# Adafruit_Feather_M0_AdaloggerTPS63001.net
KiCad netlist of a schematic drawn in EAGLE
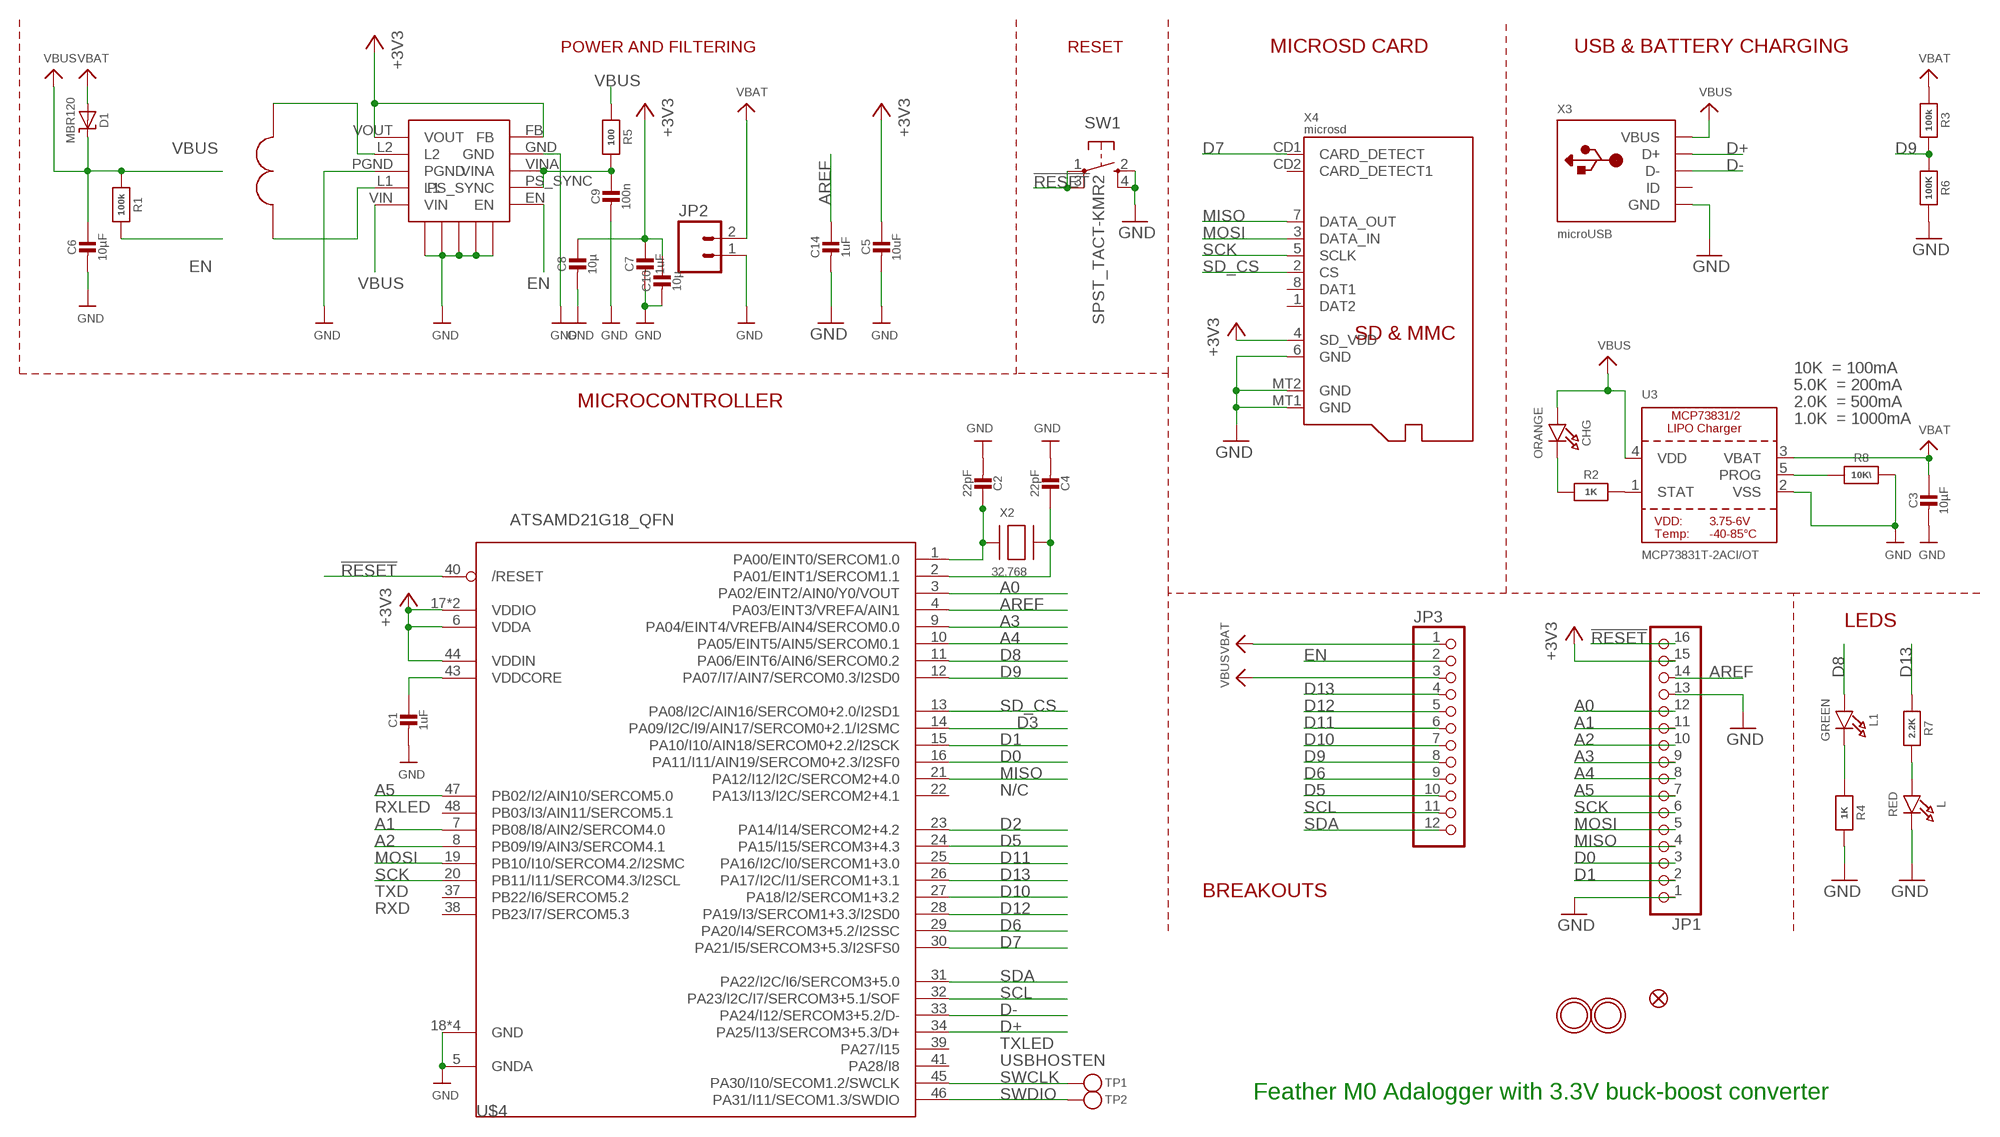
[diagram p0: schematic, sheet 1]

(export (version "E")
  (design (tool "Eeschema 10.0.6"))
  (components
    (comp (ref "C1")
      (value "1uF")
      (footprint "eagle-import:0603-NO")
      (libsource (lib "eagle-import") (part "CAP_CERAMIC0603_NO"))
    )
    (comp (ref "C2")
      (value "22pF")
      (footprint "eagle-import:0603-NO")
      (libsource (lib "eagle-import") (part "CAP_CERAMIC0603_NO"))
    )
    (comp (ref "C3")
      (value "10µF")
      (footprint "eagle-import:0805-NO")
      (libsource (lib "eagle-import") (part "CAP_CERAMIC0805-NOOUTLINE"))
    )
    (comp (ref "C4")
      (value "22pF")
      (footprint "eagle-import:0603-NO")
      (libsource (lib "eagle-import") (part "CAP_CERAMIC0603_NO"))
    )
    (comp (ref "C5")
      (value "10uF")
      (footprint "eagle-import:0805-NO")
      (libsource (lib "eagle-import") (part "CAP_CERAMIC0805-NOOUTLINE"))
    )
    (comp (ref "C6")
      (value "10µF")
      (footprint "eagle-import:0805-NO")
      (libsource (lib "eagle-import") (part "CAP_CERAMIC0805-NOOUTLINE"))
    )
    (comp (ref "C7")
      (value "1uF")
      (footprint "eagle-import:0603-NO")
      (libsource (lib "eagle-import") (part "CAP_CERAMIC0603_NO"))
    )
    (comp (ref "C8")
      (value "10µ")
      (footprint "eagle-import:0603-NO")
      (libsource (lib "eagle-import") (part "CAP_CERAMIC0603_NO"))
    )
    (comp (ref "C9")
      (value "100n")
      (footprint "eagle-import:0603-NO")
      (libsource (lib "eagle-import") (part "CAP_CERAMIC0603_NO"))
    )
    (comp (ref "C10")
      (value "10µ")
      (footprint "eagle-import:0603-NO")
      (libsource (lib "eagle-import") (part "CAP_CERAMIC0603_NO"))
    )
    (comp (ref "C14")
      (value "1uF")
      (footprint "eagle-import:0603-NO")
      (libsource (lib "eagle-import") (part "CAP_CERAMIC0603_NO"))
    )
    (comp (ref "CHG")
      (value "ORANGE")
      (footprint "eagle-import:CHIPLED_0805_NOOUTLINE")
      (libsource (lib "eagle-import") (part "LED0805_NOOUTLINE"))
    )
    (comp (ref "D1")
      (value "MBR120")
      (footprint "eagle-import:SOD-123")
      (libsource (lib "eagle-import") (part "DIODE-SCHOTTKYSOD-123"))
    )
    (comp (ref "JP1")
      (value "HEADER-1X16ROUND")
      (footprint "eagle-import:1X16_ROUND")
      (libsource (lib "eagle-import") (part "HEADER-1X16ROUND"))
    )
    (comp (ref "JP2")
      (value "M02PTH")
      (footprint "eagle-import:1X02")
      (libsource (lib "eagle-import") (part "M02PTH"))
    )
    (comp (ref "JP3")
      (value "HEADER-1X12")
      (footprint "eagle-import:1X12_ROUND")
      (libsource (lib "eagle-import") (part "HEADER-1X12"))
    )
    (comp (ref "L")
      (value "RED")
      (footprint "eagle-import:CHIPLED_0805_NOOUTLINE")
      (libsource (lib "eagle-import") (part "LED0805_NOOUTLINE"))
    )
    (comp (ref "L1")
      (value "GREEN")
      (footprint "eagle-import:CHIPLED_0805_NOOUTLINE")
      (libsource (lib "eagle-import") (part "LED0805_NOOUTLINE"))
    )
    (comp (ref "R1")
      (value "100k")
      (footprint "eagle-import:0603-NO")
      (libsource (lib "eagle-import") (part "RESISTOR_0603_NOOUT"))
    )
    (comp (ref "R2")
      (value "1K")
      (footprint "eagle-import:0603-NO")
      (libsource (lib "eagle-import") (part "RESISTOR_0603_NOOUT"))
    )
    (comp (ref "R3")
      (value "100k")
      (footprint "eagle-import:0603-NO")
      (libsource (lib "eagle-import") (part "RESISTOR_0603_NOOUT"))
    )
    (comp (ref "R4")
      (value "1K")
      (footprint "eagle-import:0603-NO")
      (libsource (lib "eagle-import") (part "RESISTOR_0603_NOOUT"))
    )
    (comp (ref "R5")
      (value "100")
      (footprint "eagle-import:0603-NO")
      (libsource (lib "eagle-import") (part "RESISTOR_0603_NOOUT"))
    )
    (comp (ref "R6")
      (value "100K")
      (footprint "eagle-import:0603-NO")
      (libsource (lib "eagle-import") (part "RESISTOR_0603_NOOUT"))
    )
    (comp (ref "R7")
      (value "2.2K")
      (footprint "eagle-import:0603-NO")
      (libsource (lib "eagle-import") (part "RESISTOR_0603_NOOUT"))
    )
    (comp (ref "R8")
      (value "10K\\")
      (footprint "eagle-import:0603-NO")
      (libsource (lib "eagle-import") (part "RESISTOR_0603_NOOUT"))
    )
    (comp (ref "SW1")
      (value "SPST_TACT-KMR2")
      (footprint "eagle-import:KMR2")
      (libsource (lib "eagle-import") (part "SPST_TACT-KMR2"))
    )
    (comp (ref "TP1")
      (value "TESTPOINTROUND1.5MM")
      (footprint "eagle-import:TESTPOINT_ROUND_1.5MM")
      (libsource (lib "eagle-import") (part "TESTPOINTROUND1.5MM"))
    )
    (comp (ref "TP2")
      (value "TESTPOINTROUND1.5MM")
      (footprint "eagle-import:TESTPOINT_ROUND_1.5MM")
      (libsource (lib "eagle-import") (part "TESTPOINTROUND1.5MM"))
    )
    (comp (ref "U$4")
      (value "ATSAMD21G18_QFN")
      (footprint "eagle-import:TQFN48_7MM")
      (libsource (lib "eagle-import") (part "ATSAMD21J_QFN"))
    )
    (comp (ref "U$12")
      (value "TPS63001")
      (footprint "eagle-import:TPS63001")
      (libsource (lib "eagle-import") (part "TPS63001"))
    )
    (comp (ref "U$15")
      (value "VLF4012A")
      (footprint "eagle-import:VLF4012A")
      (libsource (lib "eagle-import") (part "VLF4012A"))
    )
    (comp (ref "U$31")
      (value "MOUNTINGHOLE2.5")
      (footprint "eagle-import:MOUNTINGHOLE_2.5_PLATED")
      (libsource (lib "eagle-import") (part "MOUNTINGHOLE2.5"))
    )
    (comp (ref "U$32")
      (value "MOUNTINGHOLE2.5")
      (footprint "eagle-import:MOUNTINGHOLE_2.5_PLATED")
      (libsource (lib "eagle-import") (part "MOUNTINGHOLE2.5"))
    )
    (comp (ref "U$35")
      (value "FIDUCIAL\"\"")
      (footprint "eagle-import:FIDUCIAL_1MM")
      (libsource (lib "eagle-import") (part "FIDUCIAL{dblquote}{dblquote}"))
    )
    (comp (ref "U3")
      (value "MCP73831T-2ACI/OT")
      (footprint "eagle-import:SOT23-5")
      (libsource (lib "eagle-import") (part "MCP73831/2"))
    )
    (comp (ref "X2")
      (value "32.768")
      (footprint "eagle-import:XTAL3215")
      (libsource (lib "eagle-import") (part "XTAL-3.2X1.5"))
    )
    (comp (ref "X3")
      (value "microUSB")
      (footprint "eagle-import:4UCONN_20329_V2")
      (libsource (lib "eagle-import") (part "USB_MICRO_20329_V2"))
    )
    (comp (ref "X4")
      (value "microsd")
      (footprint "eagle-import:MICROSD")
      (libsource (lib "eagle-import") (part "MICROSD"))
    )
  )
  (nets
    (net (code "1") (name "+3V3") (class "Default")
      (node (ref "C10") (pin "1") (pinfunction "1_1") (pintype "passive"))
      (node (ref "C5") (pin "1") (pinfunction "1_1") (pintype "passive"))
      (node (ref "C7") (pin "1") (pinfunction "1_1") (pintype "passive"))
      (node (ref "C8") (pin "1") (pinfunction "1_1") (pintype "passive"))
      (node (ref "JP1") (pin "15") (pinfunction "15_15") (pintype "passive"))
      (node (ref "U$12") (pin "FB") (pinfunction "FB_FB") (pintype "bidirectional"))
      (node (ref "U$12") (pin "VOUT") (pinfunction "VOUT_VOUT") (pintype "bidirectional"))
      (node (ref "U$4") (pin "17") (pinfunction "VDDIO_17") (pintype "power_in"))
      (node (ref "U$4") (pin "36") (pinfunction "VDDIO_36") (pintype "power_in"))
      (node (ref "U$4") (pin "44") (pinfunction "VDDIN_44") (pintype "power_in"))
      (node (ref "U$4") (pin "6") (pinfunction "VDDA_6") (pintype "power_in"))
      (node (ref "X4") (pin "4") (pinfunction "SD_VDD_4") (pintype "power_in"))
    )
    (net (code "2") (name "/A0") (class "Default")
      (node (ref "JP1") (pin "12") (pinfunction "12_12") (pintype "passive"))
      (node (ref "U$4") (pin "3") (pinfunction "PA02/EINT2/AIN0/Y0/VOUT_3") (pintype "bidirectional"))
    )
    (net (code "3") (name "/A1") (class "Default")
      (node (ref "JP1") (pin "11") (pinfunction "11_11") (pintype "passive"))
      (node (ref "U$4") (pin "7") (pinfunction "PB08/I8/AIN2/SERCOM4.0_7") (pintype "bidirectional"))
    )
    (net (code "4") (name "/A2") (class "Default")
      (node (ref "JP1") (pin "10") (pinfunction "10_10") (pintype "passive"))
      (node (ref "U$4") (pin "8") (pinfunction "PB09/I9/AIN3/SERCOM4.1_8") (pintype "bidirectional"))
    )
    (net (code "5") (name "/A3") (class "Default")
      (node (ref "JP1") (pin "9") (pinfunction "9_9") (pintype "passive"))
      (node (ref "U$4") (pin "9") (pinfunction "PA04/EINT4/VREFB/AIN4/SERCOM0.0_9") (pintype "bidirectional"))
    )
    (net (code "6") (name "/A4") (class "Default")
      (node (ref "JP1") (pin "8") (pinfunction "8_8") (pintype "passive"))
      (node (ref "U$4") (pin "10") (pinfunction "PA05/EINT5/AIN5/SERCOM0.1_10") (pintype "bidirectional"))
    )
    (net (code "7") (name "/A5") (class "Default")
      (node (ref "JP1") (pin "7") (pinfunction "7_7") (pintype "passive"))
      (node (ref "U$4") (pin "47") (pinfunction "PB02/I2/AIN10/SERCOM5.0_47") (pintype "bidirectional"))
    )
    (net (code "8") (name "/AREF") (class "Default")
      (node (ref "C14") (pin "1") (pinfunction "1_1") (pintype "passive"))
      (node (ref "JP1") (pin "14") (pinfunction "14_14") (pintype "passive"))
      (node (ref "U$4") (pin "4") (pinfunction "PA03/EINT3/VREFA/AIN1_4") (pintype "bidirectional"))
    )
    (net (code "9") (name "/D+") (class "Default")
      (node (ref "U$4") (pin "34") (pinfunction "PA25/I13/SERCOM3+5.3/D+_34") (pintype "bidirectional"))
      (node (ref "X3") (pin "D+") (pinfunction "D+_D+") (pintype "bidirectional"))
    )
    (net (code "10") (name "/D-") (class "Default")
      (node (ref "U$4") (pin "33") (pinfunction "PA24/I12/SERCOM3+5.2/D-_33") (pintype "bidirectional"))
      (node (ref "X3") (pin "D-") (pinfunction "D-_D-") (pintype "bidirectional"))
    )
    (net (code "11") (name "/D0") (class "Default")
      (node (ref "JP1") (pin "3") (pinfunction "3_3") (pintype "passive"))
      (node (ref "U$4") (pin "16") (pinfunction "PA11/I11/AIN19/SERCOM0+2.3/I2SF0_16") (pintype "bidirectional"))
    )
    (net (code "12") (name "/D1") (class "Default")
      (node (ref "JP1") (pin "2") (pinfunction "2_2") (pintype "passive"))
      (node (ref "U$4") (pin "15") (pinfunction "PA10/I10/AIN18/SERCOM0+2.2/I2SCK_15") (pintype "bidirectional"))
    )
    (net (code "13") (name "/D2") (class "Default")
      (node (ref "U$4") (pin "23") (pinfunction "PA14/I14/SERCOM2+4.2_23") (pintype "bidirectional"))
    )
    (net (code "14") (name "/D3") (class "Default")
      (node (ref "U$4") (pin "14") (pinfunction "PA09/I2C/I9/AIN17/SERCOM0+2.1/I2SMC_14") (pintype "bidirectional"))
    )
    (net (code "15") (name "/D5") (class "Default")
      (node (ref "JP3") (pin "10") (pinfunction "10_10") (pintype "passive"))
      (node (ref "U$4") (pin "24") (pinfunction "PA15/I15/SERCOM3+4.3_24") (pintype "bidirectional"))
    )
    (net (code "16") (name "/D6") (class "Default")
      (node (ref "JP3") (pin "9") (pinfunction "9_9") (pintype "passive"))
      (node (ref "U$4") (pin "29") (pinfunction "PA20/I4/SERCOM3+5.2/I2SSC_29") (pintype "bidirectional"))
    )
    (net (code "17") (name "/D7") (class "Default")
      (node (ref "U$4") (pin "30") (pinfunction "PA21/I5/SERCOM3+5.3/I2SFS0_30") (pintype "bidirectional"))
      (node (ref "X4") (pin "CD1") (pinfunction "CARD_DETECT_CD1") (pintype "passive"))
    )
    (net (code "18") (name "/D8") (class "Default")
      (node (ref "L1") (pin "A") (pinfunction "A_A") (pintype "passive"))
      (node (ref "U$4") (pin "11") (pinfunction "PA06/EINT6/AIN6/SERCOM0.2_11") (pintype "bidirectional"))
    )
    (net (code "19") (name "/D9") (class "Default")
      (node (ref "JP3") (pin "8") (pinfunction "8_8") (pintype "passive"))
      (node (ref "R3") (pin "2") (pinfunction "2_2") (pintype "passive"))
      (node (ref "R6") (pin "1") (pinfunction "1_1") (pintype "passive"))
      (node (ref "U$4") (pin "12") (pinfunction "PA07/I7/AIN7/SERCOM0.3/I2SD0_12") (pintype "bidirectional"))
    )
    (net (code "20") (name "/D10") (class "Default")
      (node (ref "JP3") (pin "7") (pinfunction "7_7") (pintype "passive"))
      (node (ref "U$4") (pin "27") (pinfunction "PA18/I2/SERCOM1+3.2_27") (pintype "bidirectional"))
    )
    (net (code "21") (name "/D11") (class "Default")
      (node (ref "JP3") (pin "6") (pinfunction "6_6") (pintype "passive"))
      (node (ref "U$4") (pin "25") (pinfunction "PA16/I2C/I0/SERCOM1+3.0_25") (pintype "bidirectional"))
    )
    (net (code "22") (name "/D12") (class "Default")
      (node (ref "JP3") (pin "5") (pinfunction "5_5") (pintype "passive"))
      (node (ref "U$4") (pin "28") (pinfunction "PA19/I3/SERCOM1+3.3/I2SD0_28") (pintype "bidirectional"))
    )
    (net (code "23") (name "/D13") (class "Default")
      (node (ref "JP3") (pin "4") (pinfunction "4_4") (pintype "passive"))
      (node (ref "R7") (pin "1") (pinfunction "1_1") (pintype "passive"))
      (node (ref "U$4") (pin "26") (pinfunction "PA17/I2C/I1/SERCOM1+3.1_26") (pintype "bidirectional"))
    )
    (net (code "24") (name "/EN") (class "Default")
      (node (ref "JP3") (pin "2") (pinfunction "2_2") (pintype "passive"))
      (node (ref "R1") (pin "2") (pinfunction "2_2") (pintype "passive"))
      (node (ref "U$12") (pin "EN") (pinfunction "EN_EN") (pintype "bidirectional"))
    )
    (net (code "25") (name "/MISO") (class "Default")
      (node (ref "JP1") (pin "4") (pinfunction "4_4") (pintype "passive"))
      (node (ref "U$4") (pin "21") (pinfunction "PA12/I12/I2C/SERCOM2+4.0_21") (pintype "bidirectional"))
      (node (ref "X4") (pin "7") (pinfunction "DATA_OUT_7") (pintype "output"))
    )
    (net (code "26") (name "/MOSI") (class "Default")
      (node (ref "JP1") (pin "5") (pinfunction "5_5") (pintype "passive"))
      (node (ref "U$4") (pin "19") (pinfunction "PB10/I10/SERCOM4.2/I2SMC_19") (pintype "bidirectional"))
      (node (ref "X4") (pin "3") (pinfunction "DATA_IN_3") (pintype "input"))
    )
    (net (code "27") (name "/SCK") (class "Default")
      (node (ref "JP1") (pin "6") (pinfunction "6_6") (pintype "passive"))
      (node (ref "U$4") (pin "20") (pinfunction "PB11/I11/SERCOM4.3/I2SCL_20") (pintype "bidirectional"))
      (node (ref "X4") (pin "5") (pinfunction "SCLK_5") (pintype "input"))
    )
    (net (code "28") (name "/SCL") (class "Default")
      (node (ref "JP3") (pin "11") (pinfunction "11_11") (pintype "passive"))
      (node (ref "U$4") (pin "32") (pinfunction "PA23/I2C/I7/SERCOM3+5.1/SOF_32") (pintype "bidirectional"))
    )
    (net (code "29") (name "/SDA") (class "Default")
      (node (ref "JP3") (pin "12") (pinfunction "12_12") (pintype "passive"))
      (node (ref "U$4") (pin "31") (pinfunction "PA22/I2C/I6/SERCOM3+5.0_31") (pintype "bidirectional"))
    )
    (net (code "30") (name "/SD_CS") (class "Default")
      (node (ref "U$4") (pin "13") (pinfunction "PA08/I2C/AIN16/SERCOM0+2.0/I2SD1_13") (pintype "bidirectional"))
      (node (ref "X4") (pin "2") (pinfunction "CS_2") (pintype "input"))
    )
    (net (code "31") (name "/SWCLK") (class "Default")
      (node (ref "TP1") (pin "P$1") (pinfunction "P$1_P$1") (pintype "bidirectional"))
      (node (ref "U$4") (pin "45") (pinfunction "PA30/I10/SECOM1.2/SWCLK_45") (pintype "bidirectional"))
    )
    (net (code "32") (name "/SWDIO") (class "Default")
      (node (ref "TP2") (pin "P$1") (pinfunction "P$1_P$1") (pintype "bidirectional"))
      (node (ref "U$4") (pin "46") (pinfunction "PA31/I11/SECOM1.3/SWDIO_46") (pintype "bidirectional"))
    )
    (net (code "33") (name "/~{RESET}") (class "Default")
      (node (ref "JP1") (pin "16") (pinfunction "16_16") (pintype "passive"))
      (node (ref "SW1") (pin "1") (pinfunction "P_1") (pintype "passive"))
      (node (ref "SW1") (pin "3") (pinfunction "P1_3") (pintype "passive"))
      (node (ref "U$4") (pin "40") (pinfunction "/RESET_40") (pintype "bidirectional"))
    )
    (net (code "34") (name "GND") (class "Default")
      (node (ref "C1") (pin "2") (pinfunction "2_2") (pintype "passive"))
      (node (ref "C10") (pin "2") (pinfunction "2_2") (pintype "passive"))
      (node (ref "C14") (pin "2") (pinfunction "2_2") (pintype "passive"))
      (node (ref "C2") (pin "2") (pinfunction "2_2") (pintype "passive"))
      (node (ref "C3") (pin "2") (pinfunction "2_2") (pintype "passive"))
      (node (ref "C4") (pin "2") (pinfunction "2_2") (pintype "passive"))
      (node (ref "C5") (pin "2") (pinfunction "2_2") (pintype "passive"))
      (node (ref "C6") (pin "2") (pinfunction "2_2") (pintype "passive"))
      (node (ref "C7") (pin "2") (pinfunction "2_2") (pintype "passive"))
      (node (ref "C8") (pin "2") (pinfunction "2_2") (pintype "passive"))
      (node (ref "C9") (pin "2") (pinfunction "2_2") (pintype "passive"))
      (node (ref "JP1") (pin "1") (pinfunction "1_1") (pintype "passive"))
      (node (ref "JP1") (pin "13") (pinfunction "13_13") (pintype "passive"))
      (node (ref "JP2") (pin "1") (pinfunction "1_1") (pintype "passive"))
      (node (ref "L") (pin "C") (pinfunction "C_C") (pintype "passive"))
      (node (ref "R4") (pin "2") (pinfunction "2_2") (pintype "passive"))
      (node (ref "R6") (pin "2") (pinfunction "2_2") (pintype "passive"))
      (node (ref "R8") (pin "2") (pinfunction "2_2") (pintype "passive"))
      (node (ref "SW1") (pin "2") (pinfunction "S_2") (pintype "passive"))
      (node (ref "SW1") (pin "4") (pinfunction "S1_4") (pintype "passive"))
      (node (ref "U$12") (pin "GND") (pinfunction "GND_GND") (pintype "bidirectional"))
      (node (ref "U$12") (pin "GNDP1") (pinfunction "GNDP1_GNDP1") (pintype "bidirectional"))
      (node (ref "U$12") (pin "GNDP2") (pinfunction "GNDP2_GNDP2") (pintype "bidirectional"))
      (node (ref "U$12") (pin "GNDP3") (pinfunction "GNDP3_GNDP3") (pintype "bidirectional"))
      (node (ref "U$12") (pin "GNDP4") (pinfunction "GNDP4_GNDP4") (pintype "bidirectional"))
      (node (ref "U$12") (pin "GNDP5") (pinfunction "GNDP5_GNDP5") (pintype "bidirectional"))
      (node (ref "U$12") (pin "PGND") (pinfunction "PGND_PGND") (pintype "bidirectional"))
      (node (ref "U$4") (pin "18") (pinfunction "GND_18") (pintype "power_in"))
      (node (ref "U$4") (pin "35") (pinfunction "GND_35") (pintype "power_in"))
      (node (ref "U$4") (pin "42") (pinfunction "GND_42") (pintype "power_in"))
      (node (ref "U$4") (pin "5") (pinfunction "GNDA_5") (pintype "power_in"))
      (node (ref "U$4") (pin "THERMAL") (pinfunction "GND_THERMAL") (pintype "power_in"))
      (node (ref "U3") (pin "2") (pinfunction "VSS_2") (pintype "power_in"))
      (node (ref "X3") (pin "BASE@1") (pinfunction "GND_BASE@1") (pintype "power_in"))
      (node (ref "X3") (pin "BASE@2") (pinfunction "GND_BASE@2") (pintype "power_in"))
      (node (ref "X3") (pin "GND") (pinfunction "GND_GND") (pintype "power_in"))
      (node (ref "X3") (pin "SPRT@1") (pinfunction "GND_SPRT@1") (pintype "power_in"))
      (node (ref "X3") (pin "SPRT@2") (pinfunction "GND_SPRT@2") (pintype "power_in"))
      (node (ref "X3") (pin "SPRT@3") (pinfunction "GND_SPRT@3") (pintype "power_in"))
      (node (ref "X3") (pin "SPRT@4") (pinfunction "GND_SPRT@4") (pintype "power_in"))
      (node (ref "X4") (pin "6") (pinfunction "GND_6") (pintype "power_in"))
      (node (ref "X4") (pin "MT1") (pinfunction "GND_MT1") (pintype "power_in"))
      (node (ref "X4") (pin "MT2") (pinfunction "GND_MT2") (pintype "power_in"))
    )
    (net (code "35") (name "Net-(C9-Pad1)") (class "Default")
      (node (ref "C9") (pin "1") (pinfunction "1_1") (pintype "passive"))
      (node (ref "R5") (pin "2") (pinfunction "2_2") (pintype "passive"))
      (node (ref "U$12") (pin "PS_SYNC") (pinfunction "PS_SYNC_PS_SYNC") (pintype "bidirectional"))
      (node (ref "U$12") (pin "VINA") (pinfunction "VINA_VINA") (pintype "bidirectional"))
    )
    (net (code "36") (name "Net-(CHG-PadC)") (class "Default")
      (node (ref "CHG") (pin "C") (pinfunction "C_C") (pintype "passive"))
      (node (ref "R2") (pin "1") (pinfunction "1_1") (pintype "passive"))
    )
    (net (code "37") (name "Net-(L-PadA)") (class "Default")
      (node (ref "L") (pin "A") (pinfunction "A_A") (pintype "passive"))
      (node (ref "R7") (pin "2") (pinfunction "2_2") (pintype "passive"))
    )
    (net (code "38") (name "Net-(L1-PadC)") (class "Default")
      (node (ref "L1") (pin "C") (pinfunction "C_C") (pintype "passive"))
      (node (ref "R4") (pin "1") (pinfunction "1_1") (pintype "passive"))
    )
    (net (code "39") (name "Net-(U$4-PA00{slash}EINT0{slash}SERCOM1.0)") (class "Default")
      (node (ref "C2") (pin "1") (pinfunction "1_1") (pintype "passive"))
      (node (ref "U$4") (pin "1") (pinfunction "PA00/EINT0/SERCOM1.0_1") (pintype "bidirectional"))
      (node (ref "X2") (pin "P$1") (pinfunction "P$1_P$1") (pintype "bidirectional"))
    )
    (net (code "40") (name "Net-(U$4-PA01{slash}EINT1{slash}SERCOM1.1)") (class "Default")
      (node (ref "C4") (pin "1") (pinfunction "1_1") (pintype "passive"))
      (node (ref "U$4") (pin "2") (pinfunction "PA01/EINT1/SERCOM1.1_2") (pintype "bidirectional"))
      (node (ref "X2") (pin "P$2") (pinfunction "P$2_P$2") (pintype "bidirectional"))
    )
    (net (code "41") (name "Net-(U$4-VDDCORE)") (class "Default")
      (node (ref "C1") (pin "1") (pinfunction "1_1") (pintype "passive"))
      (node (ref "U$4") (pin "43") (pinfunction "VDDCORE_43") (pintype "power_in"))
    )
    (net (code "42") (name "Net-(U$12-PadL1)") (class "Default")
      (node (ref "U$12") (pin "L1") (pinfunction "L1_L1") (pintype "bidirectional"))
      (node (ref "U$15") (pin "P$1") (pinfunction "P$1_P$1") (pintype "bidirectional"))
    )
    (net (code "43") (name "Net-(U$12-PadL2)") (class "Default")
      (node (ref "U$12") (pin "L2") (pinfunction "L2_L2") (pintype "bidirectional"))
      (node (ref "U$15") (pin "P$2") (pinfunction "P$2_P$2") (pintype "bidirectional"))
    )
    (net (code "44") (name "Net-(U3-PROG)") (class "Default")
      (node (ref "R8") (pin "1") (pinfunction "1_1") (pintype "passive"))
      (node (ref "U3") (pin "5") (pinfunction "PROG_5") (pintype "input"))
    )
    (net (code "45") (name "Net-(U3-STAT)") (class "Default")
      (node (ref "R2") (pin "2") (pinfunction "2_2") (pintype "passive"))
      (node (ref "U3") (pin "1") (pinfunction "STAT_1") (pintype "output"))
    )
    (net (code "46") (name "VBAT") (class "Default")
      (node (ref "C3") (pin "1") (pinfunction "1_1") (pintype "passive"))
      (node (ref "D1") (pin "A") (pinfunction "A_A") (pintype "passive"))
      (node (ref "JP2") (pin "2") (pinfunction "2_2") (pintype "passive"))
      (node (ref "JP3") (pin "1") (pinfunction "1_1") (pintype "passive"))
      (node (ref "R3") (pin "1") (pinfunction "1_1") (pintype "passive"))
      (node (ref "U3") (pin "3") (pinfunction "VBAT_3") (pintype "power_in"))
    )
    (net (code "47") (name "VBUS") (class "Default")
      (node (ref "C6") (pin "1") (pinfunction "1_1") (pintype "passive"))
      (node (ref "CHG") (pin "A") (pinfunction "A_A") (pintype "passive"))
      (node (ref "D1") (pin "C") (pinfunction "C_C") (pintype "passive"))
      (node (ref "JP3") (pin "3") (pinfunction "3_3") (pintype "passive"))
      (node (ref "R1") (pin "1") (pinfunction "1_1") (pintype "passive"))
      (node (ref "R5") (pin "1") (pinfunction "1_1") (pintype "passive"))
      (node (ref "U$12") (pin "VIN") (pinfunction "VIN_VIN") (pintype "bidirectional"))
      (node (ref "U3") (pin "4") (pinfunction "VDD_4") (pintype "power_in"))
      (node (ref "X3") (pin "VBUS") (pinfunction "VBUS_VBUS") (pintype "power_in"))
    )
    (net (code "48") (name "unconnected-(U$4-PA13{slash}I13{slash}I2C{slash}SERCOM2+4.1-Pad22)") (class "Default")
      (node (ref "U$4") (pin "22") (pinfunction "PA13/I13/I2C/SERCOM2+4.1_22") (pintype "bidirectional"))
    )
    (net (code "49") (name "unconnected-(U$4-PA27{slash}I15-Pad39)") (class "Default")
      (node (ref "U$4") (pin "39") (pinfunction "PA27/I15_39") (pintype "bidirectional"))
    )
    (net (code "50") (name "unconnected-(U$4-PA28{slash}I8-Pad41)") (class "Default")
      (node (ref "U$4") (pin "41") (pinfunction "PA28/I8_41") (pintype "bidirectional"))
    )
    (net (code "51") (name "unconnected-(U$4-PB03{slash}I3{slash}AIN11{slash}SERCOM5.1-Pad48)") (class "Default")
      (node (ref "U$4") (pin "48") (pinfunction "PB03/I3/AIN11/SERCOM5.1_48") (pintype "bidirectional"))
    )
    (net (code "52") (name "unconnected-(U$4-PB22{slash}I6{slash}SERCOM5.2-Pad37)") (class "Default")
      (node (ref "U$4") (pin "37") (pinfunction "PB22/I6/SERCOM5.2_37") (pintype "bidirectional"))
    )
    (net (code "53") (name "unconnected-(U$4-PB23{slash}I7{slash}SERCOM5.3-Pad38)") (class "Default")
      (node (ref "U$4") (pin "38") (pinfunction "PB23/I7/SERCOM5.3_38") (pintype "bidirectional"))
    )
    (net (code "54") (name "unconnected-(X3-PadID)") (class "Default")
      (node (ref "X3") (pin "ID") (pinfunction "ID_ID") (pintype "bidirectional"))
    )
    (net (code "55") (name "unconnected-(X4-CARD_DETECT1-PadCD2)") (class "Default")
      (node (ref "X4") (pin "CD2") (pinfunction "CARD_DETECT1_CD2") (pintype "passive"))
    )
    (net (code "56") (name "unconnected-(X4-DAT1-Pad8)") (class "Default")
      (node (ref "X4") (pin "8") (pinfunction "DAT1_8") (pintype "bidirectional"))
    )
    (net (code "57") (name "unconnected-(X4-DAT2-Pad1)") (class "Default")
      (node (ref "X4") (pin "1") (pinfunction "DAT2_1") (pintype "bidirectional"))
    )
  )
)
